# TestBoard.net
KiCad netlist of a schematic drawn in EAGLE
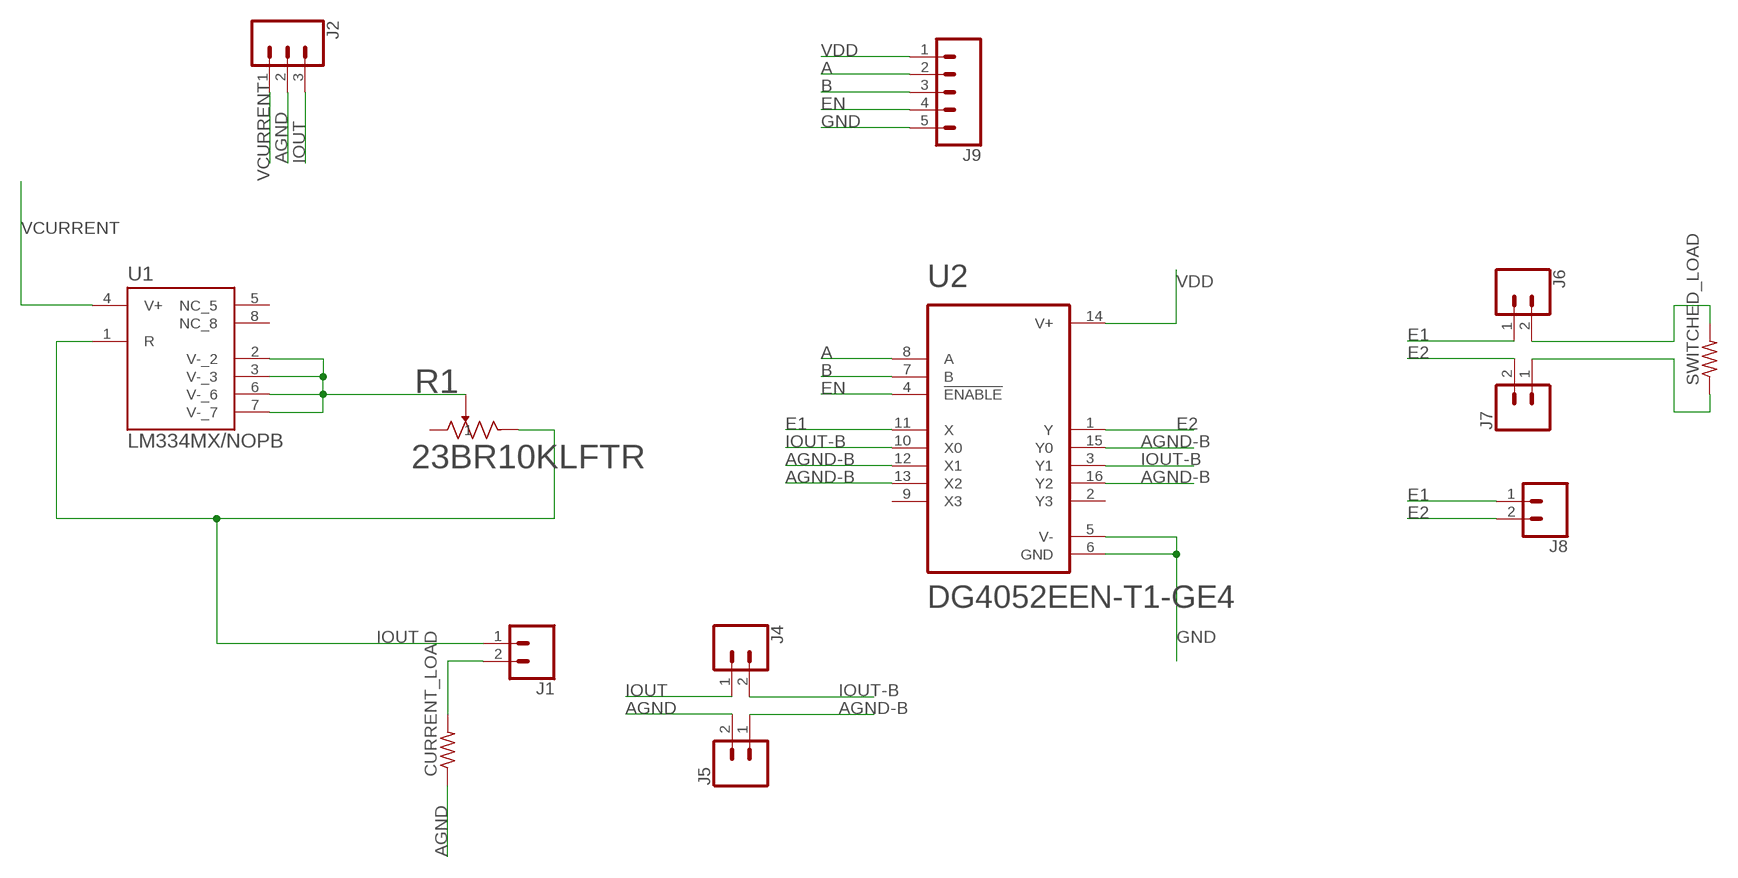
[diagram p0: schematic, sheet 1]

(export (version "E")
  (design (tool "Eeschema 10.0.6"))
  (components
    (comp (ref "CURRENT_LOAD")
      (value "R-US_V234/12")
      (footprint "eagle-import:V234_12")
      (libsource (lib "eagle-import") (part "R-US_V234/12"))
    )
    (comp (ref "J1")
      (value "CONN_02LOCK")
      (footprint "eagle-import:1X02_LOCK")
      (libsource (lib "eagle-import") (part "CONN_02LOCK"))
    )
    (comp (ref "J2")
      (value "CONN_03LOCK")
      (footprint "eagle-import:1X03_LOCK")
      (libsource (lib "eagle-import") (part "CONN_03LOCK"))
    )
    (comp (ref "J4")
      (value "CONN_02")
      (footprint "eagle-import:1X02")
      (libsource (lib "eagle-import") (part "CONN_02"))
    )
    (comp (ref "J5")
      (value "CONN_02")
      (footprint "eagle-import:1X02")
      (libsource (lib "eagle-import") (part "CONN_02"))
    )
    (comp (ref "J6")
      (value "CONN_02")
      (footprint "eagle-import:1X02")
      (libsource (lib "eagle-import") (part "CONN_02"))
    )
    (comp (ref "J7")
      (value "CONN_02")
      (footprint "eagle-import:1X02")
      (libsource (lib "eagle-import") (part "CONN_02"))
    )
    (comp (ref "J8")
      (value "CONN_02")
      (footprint "eagle-import:1X02")
      (libsource (lib "eagle-import") (part "CONN_02"))
    )
    (comp (ref "J9")
      (value "CONN_05LOCK")
      (footprint "eagle-import:1X05_LOCK")
      (libsource (lib "eagle-import") (part "CONN_05LOCK"))
    )
    (comp (ref "R1")
      (value "23BR10KLFTR")
      (footprint "eagle-import:RES3_23B_TTE")
      (fields (field (name "COPYRIGHT") "Copyright (C) 2016 Accelerated Designs. All rights reserved"))
      (libsource (lib "eagle-import") (part "23BR10KLFTR"))
    )
    (comp (ref "SWITCHED_LOAD")
      (value "R-US_V234/12")
      (footprint "eagle-import:V234_12")
      (libsource (lib "eagle-import") (part "R-US_V234/12"))
    )
    (comp (ref "U1")
      (value "LM334MX/NOPB")
      (footprint "eagle-import:SOIC127P599X175-8N")
      (fields
        (field (name "DIGI-KEY_PART_NUMBER") "LM334MX/NOPBCT-ND")
        (field (name "MF") "Texas Instruments")
      )
      (libsource (lib "eagle-import") (part "LM334MX/NOPB"))
    )
    (comp (ref "U2")
      (value "DG4052EEN-T1-GE4")
      (footprint "eagle-import:QFN40P260X180X60-16N")
      (fields (field (name "DIGI-KEY_PART_NUMBER") "DG4052EEN-T1-GE4CT-ND") (field (name "MF") "Vishay"))
      (libsource (lib "eagle-import") (part "DG4052EEN-T1-GE4"))
    )
  )
  (nets
    (net (code "1") (name "/A") (class "Default")
      (node (ref "J9") (pin "2") (pinfunction "2_2") (pintype "passive"))
      (node (ref "U2") (pin "8") (pinfunction "A_8") (pintype "input"))
    )
    (net (code "2") (name "/AGND") (class "Default")
      (node (ref "CURRENT_LOAD") (pin "1") (pinfunction "1_1") (pintype "passive"))
      (node (ref "J2") (pin "2") (pinfunction "2_2") (pintype "passive"))
      (node (ref "J5") (pin "2") (pinfunction "2_2") (pintype "passive"))
    )
    (net (code "3") (name "/AGND-B") (class "Default")
      (node (ref "J5") (pin "1") (pinfunction "1_1") (pintype "passive"))
      (node (ref "U2") (pin "12") (pinfunction "X1_12") (pintype "passive"))
      (node (ref "U2") (pin "13") (pinfunction "X2_13") (pintype "passive"))
      (node (ref "U2") (pin "15") (pinfunction "Y0_15") (pintype "passive"))
      (node (ref "U2") (pin "16") (pinfunction "Y2_16") (pintype "passive"))
    )
    (net (code "4") (name "/B") (class "Default")
      (node (ref "J9") (pin "3") (pinfunction "3_3") (pintype "passive"))
      (node (ref "U2") (pin "7") (pinfunction "B_7") (pintype "input"))
    )
    (net (code "5") (name "/E1") (class "Default")
      (node (ref "J6") (pin "1") (pinfunction "1_1") (pintype "passive"))
      (node (ref "J8") (pin "1") (pinfunction "1_1") (pintype "passive"))
      (node (ref "U2") (pin "11") (pinfunction "X_11") (pintype "passive"))
    )
    (net (code "6") (name "/E2") (class "Default")
      (node (ref "J7") (pin "2") (pinfunction "2_2") (pintype "passive"))
      (node (ref "J8") (pin "2") (pinfunction "2_2") (pintype "passive"))
      (node (ref "U2") (pin "1") (pinfunction "Y_1") (pintype "passive"))
    )
    (net (code "7") (name "/EN") (class "Default")
      (node (ref "J9") (pin "4") (pinfunction "4_4") (pintype "passive"))
      (node (ref "U2") (pin "4") (pinfunction "~{ENABLE}_4") (pintype "input"))
    )
    (net (code "8") (name "/GND") (class "Default")
      (node (ref "J9") (pin "5") (pinfunction "5_5") (pintype "passive"))
      (node (ref "U2") (pin "5") (pinfunction "V-_5") (pintype "power_in"))
      (node (ref "U2") (pin "6") (pinfunction "GND_6") (pintype "power_in"))
    )
    (net (code "9") (name "/IOUT") (class "Default")
      (node (ref "J1") (pin "1") (pinfunction "1_1") (pintype "passive"))
      (node (ref "J2") (pin "3") (pinfunction "3_3") (pintype "passive"))
      (node (ref "J4") (pin "1") (pinfunction "1_1") (pintype "passive"))
      (node (ref "R1") (pin "3") (pinfunction "3_3") (pintype "passive"))
      (node (ref "U1") (pin "1") (pinfunction "R_1") (pintype "passive"))
    )
    (net (code "10") (name "/IOUT-B") (class "Default")
      (node (ref "J4") (pin "2") (pinfunction "2_2") (pintype "passive"))
      (node (ref "U2") (pin "10") (pinfunction "X0_10") (pintype "passive"))
      (node (ref "U2") (pin "3") (pinfunction "Y1_3") (pintype "passive"))
    )
    (net (code "11") (name "/VCURRENT") (class "Default")
      (node (ref "J2") (pin "1") (pinfunction "1_1") (pintype "passive"))
      (node (ref "U1") (pin "4") (pinfunction "V+_4") (pintype "power_in"))
    )
    (net (code "12") (name "/VDD") (class "Default")
      (node (ref "J9") (pin "1") (pinfunction "1_1") (pintype "passive"))
      (node (ref "U2") (pin "14") (pinfunction "V+_14") (pintype "power_in"))
    )
    (net (code "13") (name "Net-(CURRENT_LOAD-Pad2)") (class "Default")
      (node (ref "CURRENT_LOAD") (pin "2") (pinfunction "2_2") (pintype "passive"))
      (node (ref "J1") (pin "2") (pinfunction "2_2") (pintype "passive"))
    )
    (net (code "14") (name "Net-(J6-Pad2)") (class "Default")
      (node (ref "J6") (pin "2") (pinfunction "2_2") (pintype "passive"))
      (node (ref "SWITCHED_LOAD") (pin "2") (pinfunction "2_2") (pintype "passive"))
    )
    (net (code "15") (name "Net-(J7-Pad1)") (class "Default")
      (node (ref "J7") (pin "1") (pinfunction "1_1") (pintype "passive"))
      (node (ref "SWITCHED_LOAD") (pin "1") (pinfunction "1_1") (pintype "passive"))
    )
    (net (code "16") (name "Net-(U1-V-_2)") (class "Default")
      (node (ref "R1") (pin "2") (pinfunction "2_2") (pintype "passive"))
      (node (ref "U1") (pin "2") (pinfunction "V-_2_2") (pintype "power_in"))
      (node (ref "U1") (pin "3") (pinfunction "V-_3_3") (pintype "power_in"))
      (node (ref "U1") (pin "6") (pinfunction "V-_6_6") (pintype "power_in"))
      (node (ref "U1") (pin "7") (pinfunction "V-_7_7") (pintype "power_in"))
    )
    (net (code "17") (name "unconnected-(R1-Pad1)") (class "Default")
      (node (ref "R1") (pin "1") (pinfunction "1_1") (pintype "passive"))
    )
    (net (code "18") (name "unconnected-(U1-NC_5-Pad5)") (class "Default")
      (node (ref "U1") (pin "5") (pinfunction "NC_5_5") (pintype "passive"))
    )
    (net (code "19") (name "unconnected-(U1-NC_8-Pad8)") (class "Default")
      (node (ref "U1") (pin "8") (pinfunction "NC_8_8") (pintype "passive"))
    )
    (net (code "20") (name "unconnected-(U2-X3-Pad9)") (class "Default")
      (node (ref "U2") (pin "9") (pinfunction "X3_9") (pintype "passive"))
    )
    (net (code "21") (name "unconnected-(U2-Y3-Pad2)") (class "Default")
      (node (ref "U2") (pin "2") (pinfunction "Y3_2") (pintype "passive"))
    )
  )
)
